# SmokeNEW.net
KiCad netlist of a schematic drawn in EasyEDA
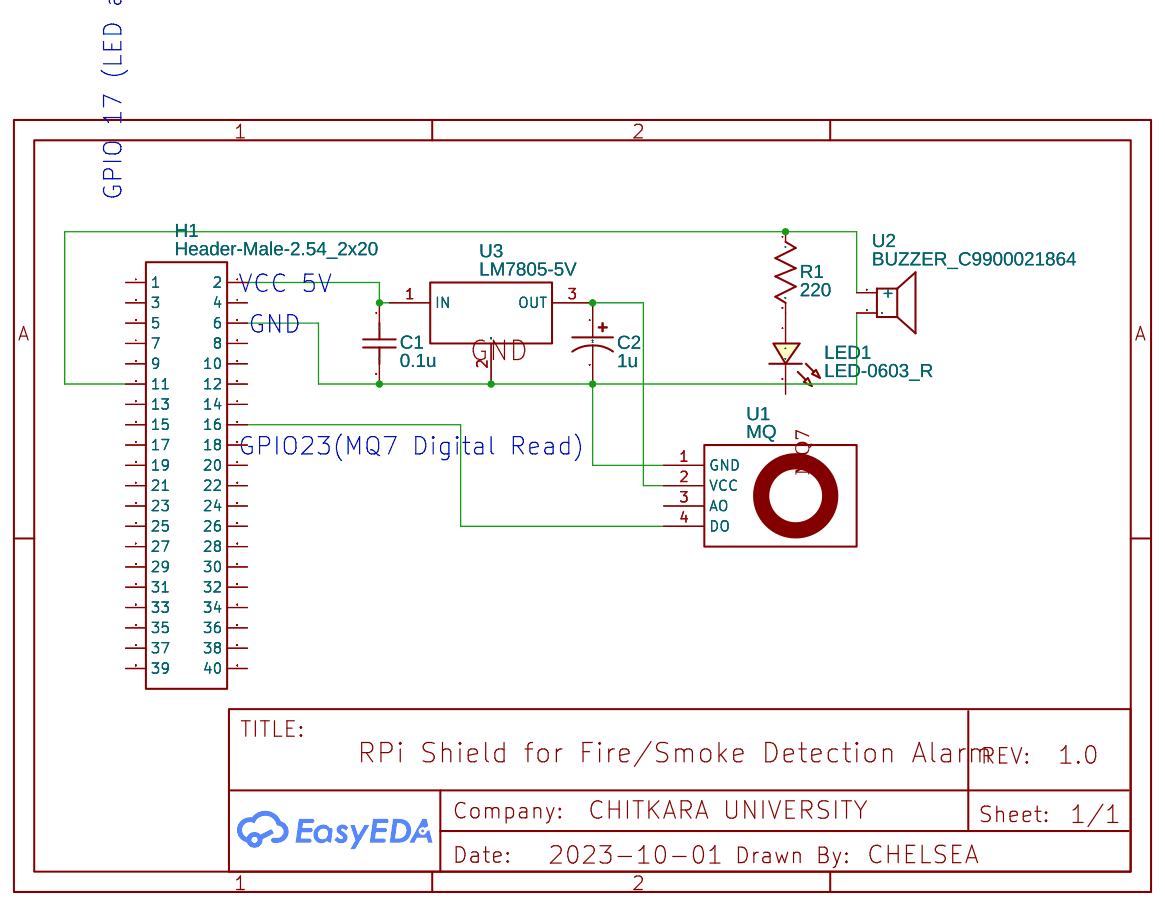
[diagram p0: schematic sheet]

(export (version "E")
  (design (tool "Eeschema 10.0.6"))
  (components
    (comp (ref "C1") (value "0.1u") (libsource (lib "") (part "C_0603_US")))
    (comp (ref "C2") (value "1u") (libsource (lib "") (part "C_Tan_SMD_A_US")))
    (comp (ref "H1")
      (value "Header-Male-2.54_2x20")
      (fields
        (field (name "Manufacturer Part") "2.54mm 2*20P直排针")
        (field (name "Manufacturer") "BOOMELE(博穆精密)")
      )
      (libsource (lib "") (part "Header-Male-2.54_2x20"))
    )
    (comp (ref "LED1")
      (value "LED-0603_R")
      (fields
        (field (name "Manufacturer Part") "19-217/R6C-AL1M2VY/3T")
        (field (name "Manufacturer") "EVERLIGHT(台湾亿光)")
      )
      (libsource (lib "") (part "LED-0603_R"))
    )
    (comp (ref "R1") (value "220") (libsource (lib "") (part "R_0603_US")))
    (comp (ref "U1") (value "MQ") (libsource (lib "") (part "MQ")))
    (comp (ref "U2")
      (value "BUZZER_C9900021864")
      (fields (field (name "Manufacturer Part") "BUZZER"))
      (libsource (lib "") (part "BUZZER_C9900021864"))
    )
    (comp (ref "U3") (value "LM7805-5V") (libsource (lib "") (part "LM7805-5V")))
  )
  (nets
    (net (code "1") (name "Net-(LED1-Pad1)") (class "Default")
      (node (ref "LED1") (pin "1") (pinfunction "1_1") (pintype "unspecified"))
      (node (ref "R1") (pin "2") (pinfunction "2_2") (pintype "unspecified"))
    )
    (net (code "2") (name "Net-(U1-DO)") (class "Default")
      (node (ref "H1") (pin "16") (pinfunction "16_16") (pintype "input"))
      (node (ref "U1") (pin "4") (pinfunction "DO_4") (pintype "unspecified"))
    )
    (net (code "3") (name "Net-(U1-GND)") (class "Default")
      (node (ref "C1") (pin "2") (pinfunction "2_2") (pintype "unspecified"))
      (node (ref "C2") (pin "2") (pinfunction "2_2") (pintype "unspecified"))
      (node (ref "H1") (pin "6") (pinfunction "6_6") (pintype "input"))
      (node (ref "U1") (pin "1") (pinfunction "GND_1") (pintype "unspecified"))
      (node (ref "U2") (pin "1") (pinfunction "1_1") (pintype "unspecified"))
      (node (ref "U3") (pin "2") (pinfunction "GND_2") (pintype "passive"))
    )
    (net (code "4") (name "Net-(U1-VCC)") (class "Default")
      (node (ref "C2") (pin "1") (pinfunction "1_1") (pintype "unspecified"))
      (node (ref "U1") (pin "2") (pinfunction "VCC_2") (pintype "unspecified"))
      (node (ref "U3") (pin "3") (pinfunction "OUT_3") (pintype "passive"))
    )
    (net (code "5") (name "Net-(U2-+)") (class "Default")
      (node (ref "H1") (pin "11") (pinfunction "11_11") (pintype "input"))
      (node (ref "R1") (pin "1") (pinfunction "1_1") (pintype "unspecified"))
      (node (ref "U2") (pin "2") (pinfunction "+_2") (pintype "unspecified"))
    )
    (net (code "6") (name "Net-(U3-IN)") (class "Default")
      (node (ref "C1") (pin "1") (pinfunction "1_1") (pintype "unspecified"))
      (node (ref "H1") (pin "2") (pinfunction "2_2") (pintype "input"))
      (node (ref "U3") (pin "1") (pinfunction "IN_1") (pintype "passive"))
    )
    (net (code "7") (name "unconnected-(H1-Pad1)") (class "Default")
      (node (ref "H1") (pin "1") (pinfunction "1_1") (pintype "input"))
    )
    (net (code "8") (name "unconnected-(H1-Pad3)") (class "Default")
      (node (ref "H1") (pin "3") (pinfunction "3_3") (pintype "input"))
    )
    (net (code "9") (name "unconnected-(H1-Pad4)") (class "Default")
      (node (ref "H1") (pin "4") (pinfunction "4_4") (pintype "input"))
    )
    (net (code "10") (name "unconnected-(H1-Pad5)") (class "Default")
      (node (ref "H1") (pin "5") (pinfunction "5_5") (pintype "input"))
    )
    (net (code "11") (name "unconnected-(H1-Pad7)") (class "Default")
      (node (ref "H1") (pin "7") (pinfunction "7_7") (pintype "input"))
    )
    (net (code "12") (name "unconnected-(H1-Pad8)") (class "Default")
      (node (ref "H1") (pin "8") (pinfunction "8_8") (pintype "input"))
    )
    (net (code "13") (name "unconnected-(H1-Pad9)") (class "Default")
      (node (ref "H1") (pin "9") (pinfunction "9_9") (pintype "input"))
    )
    (net (code "14") (name "unconnected-(H1-Pad10)") (class "Default")
      (node (ref "H1") (pin "10") (pinfunction "10_10") (pintype "input"))
    )
    (net (code "15") (name "unconnected-(H1-Pad12)") (class "Default")
      (node (ref "H1") (pin "12") (pinfunction "12_12") (pintype "input"))
    )
    (net (code "16") (name "unconnected-(H1-Pad13)") (class "Default")
      (node (ref "H1") (pin "13") (pinfunction "13_13") (pintype "input"))
    )
    (net (code "17") (name "unconnected-(H1-Pad14)") (class "Default")
      (node (ref "H1") (pin "14") (pinfunction "14_14") (pintype "input"))
    )
    (net (code "18") (name "unconnected-(H1-Pad15)") (class "Default")
      (node (ref "H1") (pin "15") (pinfunction "15_15") (pintype "input"))
    )
    (net (code "19") (name "unconnected-(H1-Pad17)") (class "Default")
      (node (ref "H1") (pin "17") (pinfunction "17_17") (pintype "input"))
    )
    (net (code "20") (name "unconnected-(H1-Pad18)") (class "Default")
      (node (ref "H1") (pin "18") (pinfunction "18_18") (pintype "input"))
    )
    (net (code "21") (name "unconnected-(H1-Pad19)") (class "Default")
      (node (ref "H1") (pin "19") (pinfunction "19_19") (pintype "input"))
    )
    (net (code "22") (name "unconnected-(H1-Pad20)") (class "Default")
      (node (ref "H1") (pin "20") (pinfunction "20_20") (pintype "input"))
    )
    (net (code "23") (name "unconnected-(H1-Pad21)") (class "Default")
      (node (ref "H1") (pin "21") (pinfunction "21_21") (pintype "input"))
    )
    (net (code "24") (name "unconnected-(H1-Pad22)") (class "Default")
      (node (ref "H1") (pin "22") (pinfunction "22_22") (pintype "input"))
    )
    (net (code "25") (name "unconnected-(H1-Pad23)") (class "Default")
      (node (ref "H1") (pin "23") (pinfunction "23_23") (pintype "input"))
    )
    (net (code "26") (name "unconnected-(H1-Pad24)") (class "Default")
      (node (ref "H1") (pin "24") (pinfunction "24_24") (pintype "input"))
    )
    (net (code "27") (name "unconnected-(H1-Pad25)") (class "Default")
      (node (ref "H1") (pin "25") (pinfunction "25_25") (pintype "input"))
    )
    (net (code "28") (name "unconnected-(H1-Pad26)") (class "Default")
      (node (ref "H1") (pin "26") (pinfunction "26_26") (pintype "input"))
    )
    (net (code "29") (name "unconnected-(H1-Pad27)") (class "Default")
      (node (ref "H1") (pin "27") (pinfunction "27_27") (pintype "input"))
    )
    (net (code "30") (name "unconnected-(H1-Pad28)") (class "Default")
      (node (ref "H1") (pin "28") (pinfunction "28_28") (pintype "input"))
    )
    (net (code "31") (name "unconnected-(H1-Pad29)") (class "Default")
      (node (ref "H1") (pin "29") (pinfunction "29_29") (pintype "input"))
    )
    (net (code "32") (name "unconnected-(H1-Pad30)") (class "Default")
      (node (ref "H1") (pin "30") (pinfunction "30_30") (pintype "input"))
    )
    (net (code "33") (name "unconnected-(H1-Pad31)") (class "Default")
      (node (ref "H1") (pin "31") (pinfunction "31_31") (pintype "input"))
    )
    (net (code "34") (name "unconnected-(H1-Pad32)") (class "Default")
      (node (ref "H1") (pin "32") (pinfunction "32_32") (pintype "input"))
    )
    (net (code "35") (name "unconnected-(H1-Pad33)") (class "Default")
      (node (ref "H1") (pin "33") (pinfunction "33_33") (pintype "input"))
    )
    (net (code "36") (name "unconnected-(H1-Pad34)") (class "Default")
      (node (ref "H1") (pin "34") (pinfunction "34_34") (pintype "input"))
    )
    (net (code "37") (name "unconnected-(H1-Pad35)") (class "Default")
      (node (ref "H1") (pin "35") (pinfunction "35_35") (pintype "input"))
    )
    (net (code "38") (name "unconnected-(H1-Pad36)") (class "Default")
      (node (ref "H1") (pin "36") (pinfunction "36_36") (pintype "input"))
    )
    (net (code "39") (name "unconnected-(H1-Pad37)") (class "Default")
      (node (ref "H1") (pin "37") (pinfunction "37_37") (pintype "input"))
    )
    (net (code "40") (name "unconnected-(H1-Pad38)") (class "Default")
      (node (ref "H1") (pin "38") (pinfunction "38_38") (pintype "input"))
    )
    (net (code "41") (name "unconnected-(H1-Pad39)") (class "Default")
      (node (ref "H1") (pin "39") (pinfunction "39_39") (pintype "input"))
    )
    (net (code "42") (name "unconnected-(H1-Pad40)") (class "Default")
      (node (ref "H1") (pin "40") (pinfunction "40_40") (pintype "input"))
    )
    (net (code "43") (name "unconnected-(LED1-Pad2)") (class "Default")
      (node (ref "LED1") (pin "2") (pinfunction "2_2") (pintype "unspecified"))
    )
    (net (code "44") (name "unconnected-(U1-AO-Pad3)") (class "Default")
      (node (ref "U1") (pin "3") (pinfunction "AO_3") (pintype "unspecified"))
    )
  )
)
